# WC_Lower_v2_1.net
KiCad netlist of a schematic drawn in EAGLE
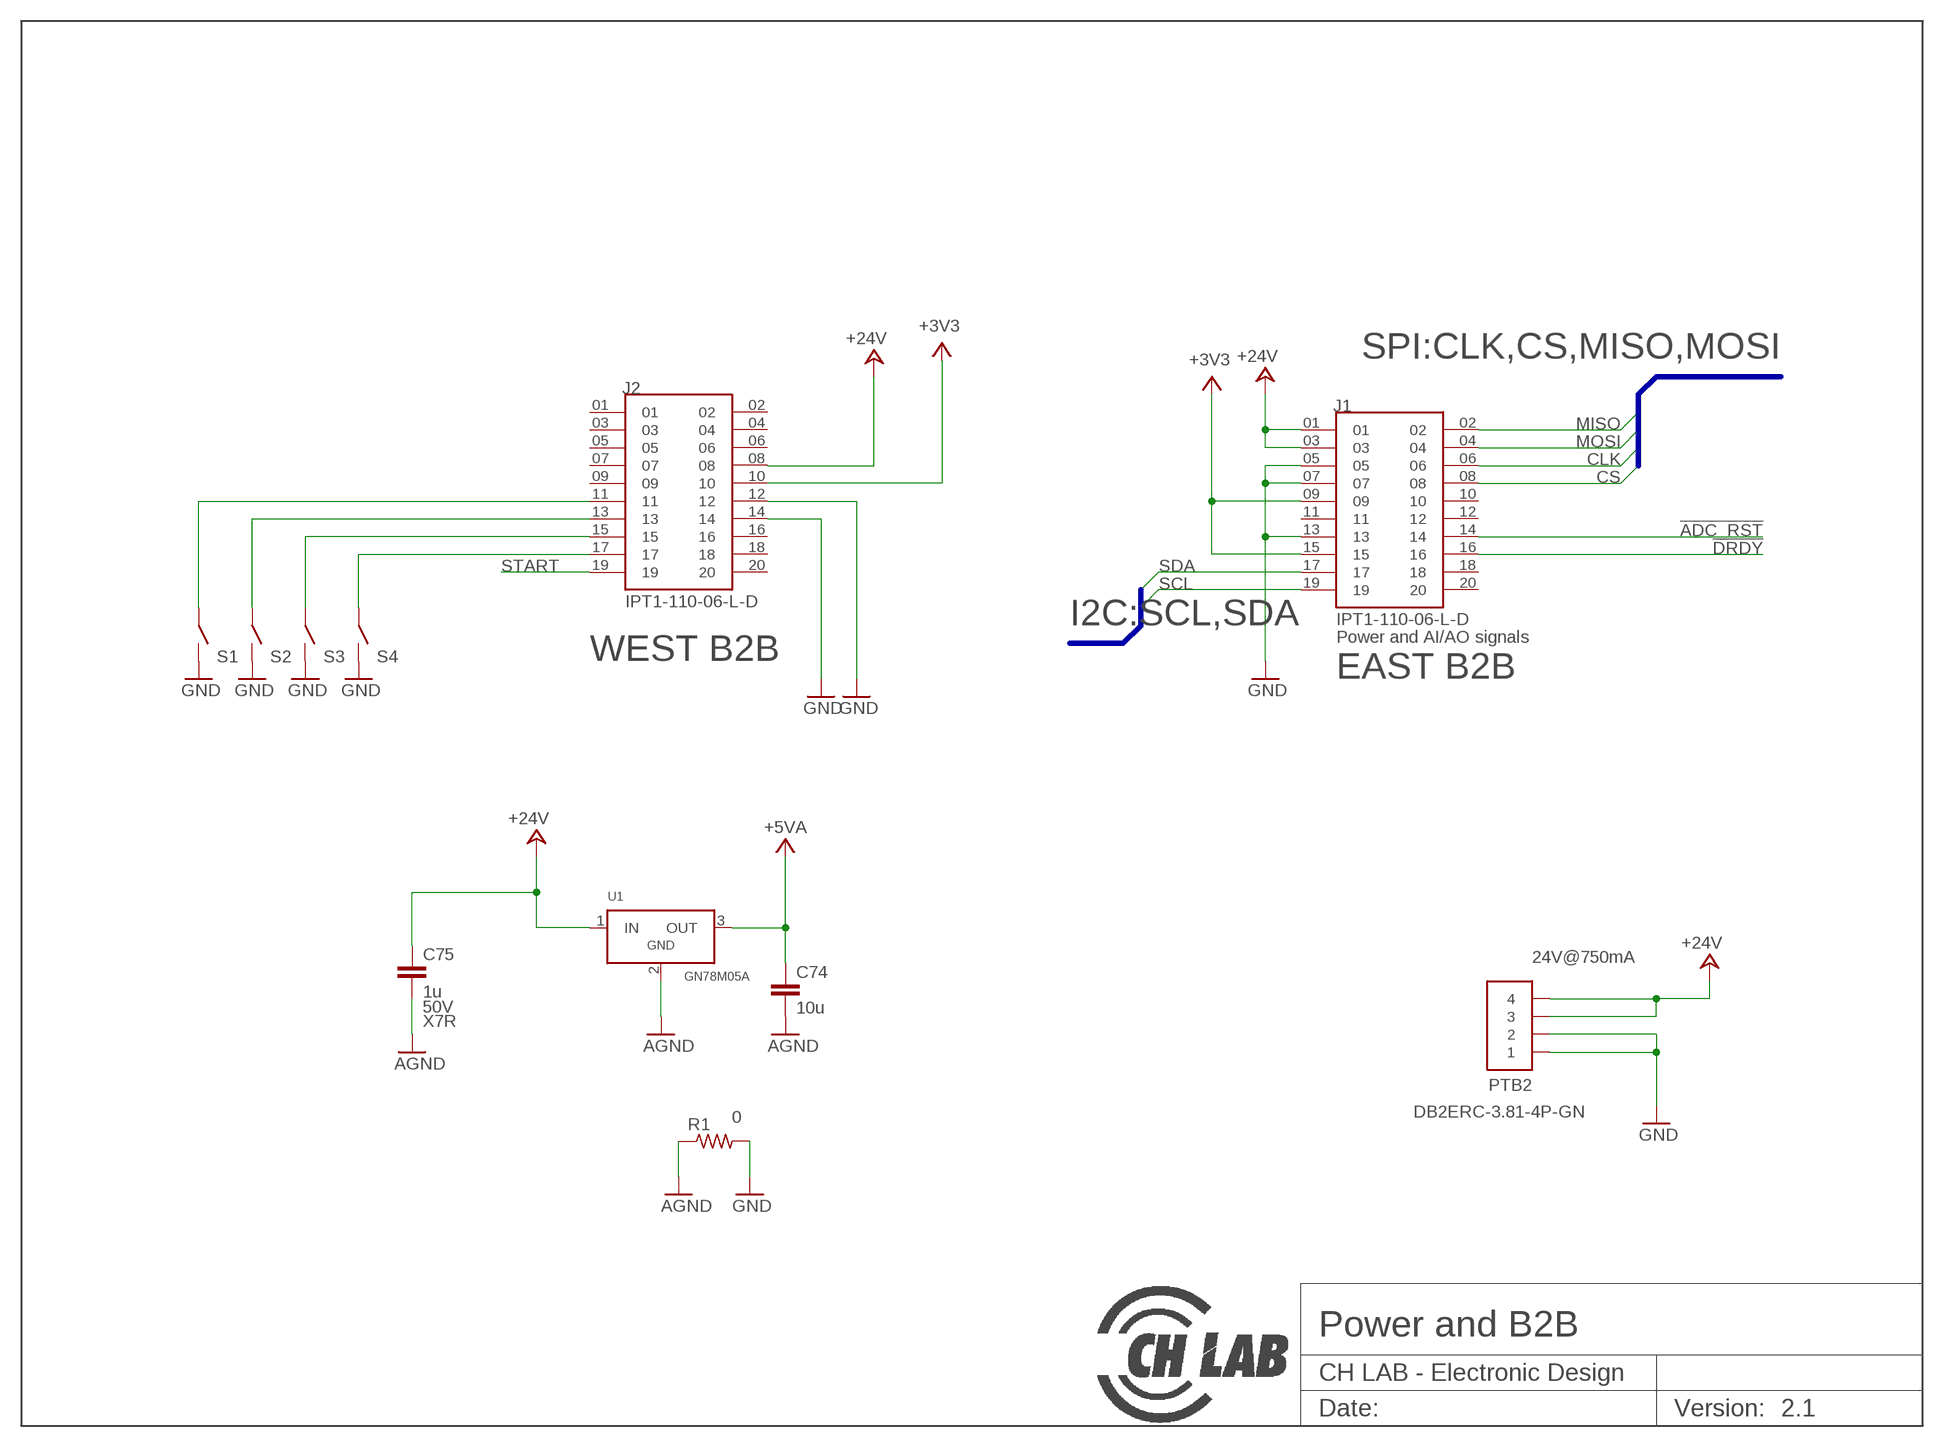
[diagram p0: schematic, sheet 1]
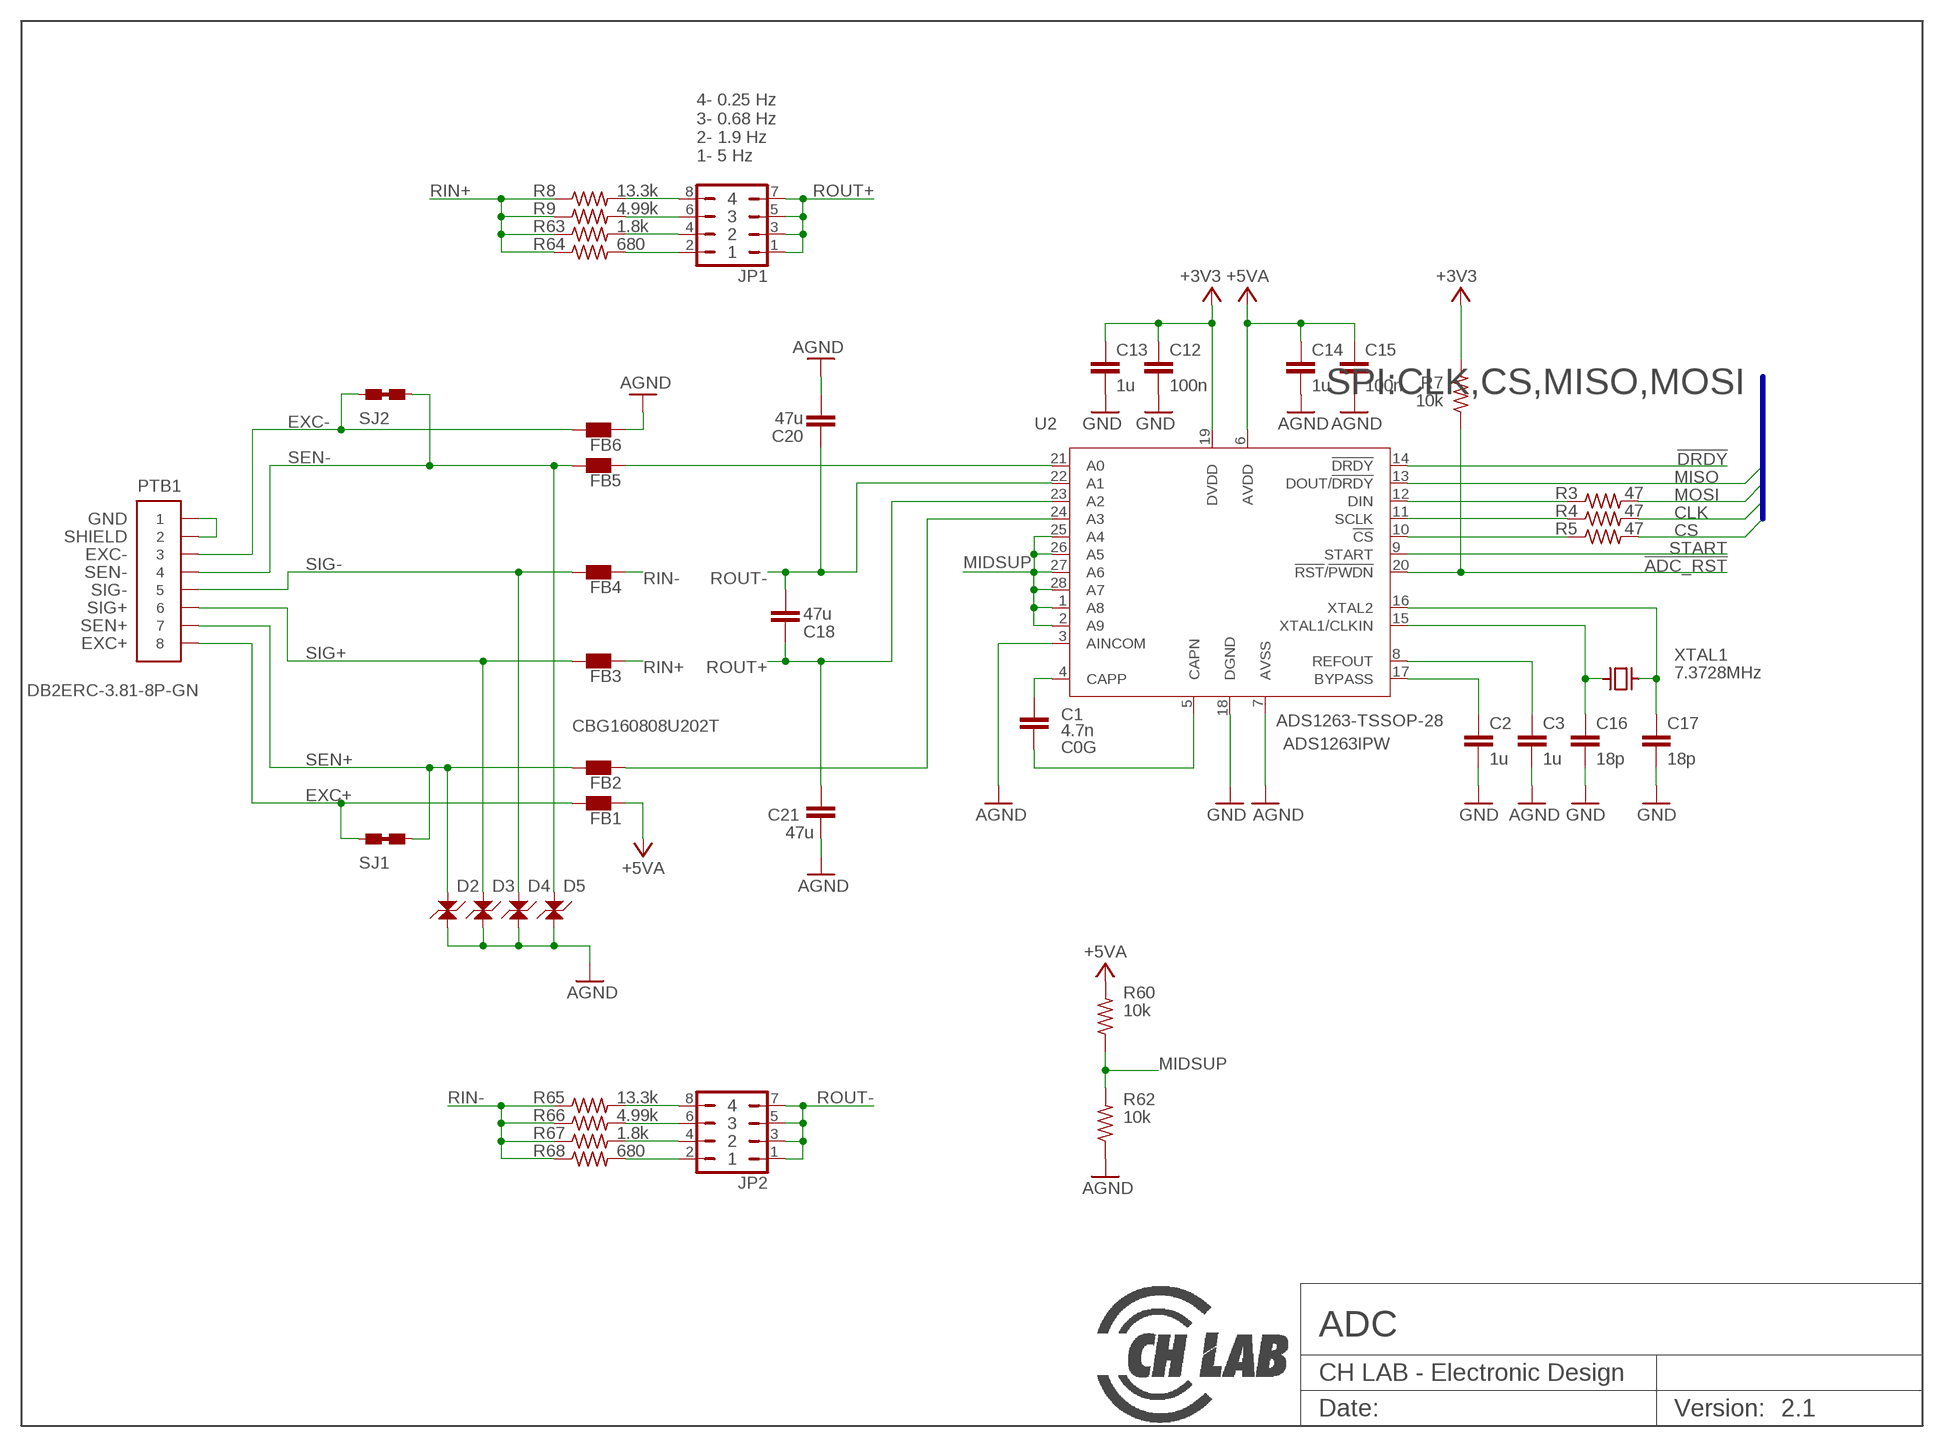
[diagram p1: schematic, sheet 2]

(export (version "E")
  (design (tool "Eeschema 10.0.6"))
  (components
    (comp (ref "C1")
      (value "4.7n")
      (footprint "eagle-import:C_0603")
      (fields (field (name "DK") "C0G"))
      (libsource (lib "eagle-import") (part "C_0603"))
    )
    (comp (ref "C2")
      (value "1u")
      (footprint "eagle-import:C_0603")
      (libsource (lib "eagle-import") (part "C_0603"))
    )
    (comp (ref "C3")
      (value "1u")
      (footprint "eagle-import:C_0603")
      (libsource (lib "eagle-import") (part "C_0603"))
    )
    (comp (ref "C12")
      (value "100n")
      (footprint "eagle-import:C_0603")
      (libsource (lib "eagle-import") (part "C_0603"))
    )
    (comp (ref "C13")
      (value "1u")
      (footprint "eagle-import:C_0603")
      (libsource (lib "eagle-import") (part "C_0603"))
    )
    (comp (ref "C14")
      (value "1u")
      (footprint "eagle-import:C_0603")
      (libsource (lib "eagle-import") (part "C_0603"))
    )
    (comp (ref "C15")
      (value "100n")
      (footprint "eagle-import:C_0603")
      (libsource (lib "eagle-import") (part "C_0603"))
    )
    (comp (ref "C16")
      (value "18p")
      (footprint "eagle-import:C_0603")
      (libsource (lib "eagle-import") (part "C_0603"))
    )
    (comp (ref "C17")
      (value "18p")
      (footprint "eagle-import:C_0603")
      (libsource (lib "eagle-import") (part "C_0603"))
    )
    (comp (ref "C18")
      (value "47u")
      (footprint "eagle-import:C_1210")
      (libsource (lib "eagle-import") (part "C_1210"))
    )
    (comp (ref "C20")
      (value "47u")
      (footprint "eagle-import:C_1210")
      (libsource (lib "eagle-import") (part "C_1210"))
    )
    (comp (ref "C21")
      (value "47u")
      (footprint "eagle-import:C_1210")
      (libsource (lib "eagle-import") (part "C_1210"))
    )
    (comp (ref "D2")
      (value "LESD5D5.0CT1G")
      (footprint "eagle-import:SOD523")
      (libsource (lib "eagle-import") (part "LESD5D5.0CT1G"))
    )
    (comp (ref "D3")
      (value "LESD5D5.0CT1G")
      (footprint "eagle-import:SOD523")
      (libsource (lib "eagle-import") (part "LESD5D5.0CT1G"))
    )
    (comp (ref "D4")
      (value "LESD5D5.0CT1G")
      (footprint "eagle-import:SOD523")
      (libsource (lib "eagle-import") (part "LESD5D5.0CT1G"))
    )
    (comp (ref "D5")
      (value "LESD5D5.0CT1G")
      (footprint "eagle-import:SOD523")
      (libsource (lib "eagle-import") (part "LESD5D5.0CT1G"))
    )
    (comp (ref "FB1")
      (value "FB_0603")
      (footprint "eagle-import:R_0603")
      (libsource (lib "eagle-import") (part "FB_0603"))
    )
    (comp (ref "FB2")
      (value "FB_0603")
      (footprint "eagle-import:R_0603")
      (libsource (lib "eagle-import") (part "FB_0603"))
    )
    (comp (ref "FB3")
      (value "FB_0603")
      (footprint "eagle-import:R_0603")
      (libsource (lib "eagle-import") (part "FB_0603"))
    )
    (comp (ref "FB4")
      (value "FB_0603")
      (footprint "eagle-import:R_0603")
      (libsource (lib "eagle-import") (part "FB_0603"))
    )
    (comp (ref "FB5")
      (value "FB_0603")
      (footprint "eagle-import:R_0603")
      (libsource (lib "eagle-import") (part "FB_0603"))
    )
    (comp (ref "FB6")
      (value "FB_0603")
      (footprint "eagle-import:R_0603")
      (libsource (lib "eagle-import") (part "FB_0603"))
    )
    (comp (ref "JP1")
      (value "CONVERT-2X4-2.54MALE")
      (footprint "eagle-import:CONN-VERT-2.54MM-2X4-MALE")
      (libsource (lib "eagle-import") (part "CONVERT-2X4-2.54MALE"))
    )
    (comp (ref "JP2")
      (value "CONVERT-2X4-2.54MALE")
      (footprint "eagle-import:CONN-VERT-2.54MM-2X4-MALE")
      (libsource (lib "eagle-import") (part "CONVERT-2X4-2.54MALE"))
    )
    (comp (ref "PTB1")
      (value "DB2ERC-3.81-8P-GN")
      (footprint "eagle-import:1803332")
      (libsource (lib "eagle-import") (part "PLUGTB-8-1803332"))
    )
    (comp (ref "R3")
      (value "47")
      (footprint "eagle-import:R_0402")
      (libsource (lib "eagle-import") (part "R_0402"))
    )
    (comp (ref "R4")
      (value "47")
      (footprint "eagle-import:R_0402")
      (libsource (lib "eagle-import") (part "R_0402"))
    )
    (comp (ref "R5")
      (value "47")
      (footprint "eagle-import:R_0402")
      (libsource (lib "eagle-import") (part "R_0402"))
    )
    (comp (ref "R7")
      (value "10k")
      (footprint "eagle-import:R_0603")
      (libsource (lib "eagle-import") (part "R_0603"))
    )
    (comp (ref "R8")
      (value "13.3k")
      (footprint "eagle-import:R_0603")
      (libsource (lib "eagle-import") (part "R_0603"))
    )
    (comp (ref "R9")
      (value "4.99k")
      (footprint "eagle-import:R_0603")
      (libsource (lib "eagle-import") (part "R_0603"))
    )
    (comp (ref "R60")
      (value "10k")
      (footprint "eagle-import:R_0603")
      (libsource (lib "eagle-import") (part "R_0603"))
    )
    (comp (ref "R62")
      (value "10k")
      (footprint "eagle-import:R_0603")
      (libsource (lib "eagle-import") (part "R_0603"))
    )
    (comp (ref "R63")
      (value "1.8k")
      (footprint "eagle-import:R_0603")
      (libsource (lib "eagle-import") (part "R_0603"))
    )
    (comp (ref "R64")
      (value "680")
      (footprint "eagle-import:R_0603")
      (libsource (lib "eagle-import") (part "R_0603"))
    )
    (comp (ref "R65")
      (value "13.3k")
      (footprint "eagle-import:R_0603")
      (libsource (lib "eagle-import") (part "R_0603"))
    )
    (comp (ref "R66")
      (value "4.99k")
      (footprint "eagle-import:R_0603")
      (libsource (lib "eagle-import") (part "R_0603"))
    )
    (comp (ref "R67")
      (value "1.8k")
      (footprint "eagle-import:R_0603")
      (libsource (lib "eagle-import") (part "R_0603"))
    )
    (comp (ref "R68")
      (value "680")
      (footprint "eagle-import:R_0603")
      (libsource (lib "eagle-import") (part "R_0603"))
    )
    (comp (ref "SJ1")
      (value "SJUMPER-NC")
      (footprint "eagle-import:SJ1")
      (libsource (lib "eagle-import") (part "SJUMPER-NC"))
    )
    (comp (ref "SJ2")
      (value "SJUMPER-NC")
      (footprint "eagle-import:SJ1")
      (libsource (lib "eagle-import") (part "SJUMPER-NC"))
    )
    (comp (ref "U2")
      (value "ADS1263-TSSOP-28")
      (footprint "eagle-import:SOP65P640X120-28N")
      (fields (field (name "MPN") "ADS1263IPW"))
      (libsource (lib "eagle-import") (part "ADS1263-TSSOP-28"))
    )
    (comp (ref "XTAL1")
      (value "7.3728MHz")
      (footprint "eagle-import:XTAL")
      (fields
        (field (name "LINK") "https://www.mouser.com/ProductDetail/ABRACON/ABLS-7.3728MHZ-K4T?qs=uDmhV2jwPReaiEAs5bxjfg%3D%3D")
        (field (name "MPN") "ABLS-7.3728MHZ-K4T")
      )
      (libsource (lib "eagle-import") (part "XTAL_11.4X4.7"))
    )
    (comp (ref "C74")
      (value "10u")
      (footprint "eagle-import:C_0805")
      (libsource (lib "eagle-import") (part "C_0805"))
    )
    (comp (ref "C75")
      (value "1u")
      (footprint "eagle-import:C_1206")
      (fields (field (name "D") "X7R") (field (name "ESR") "LOW") (field (name "V") "50V"))
      (libsource (lib "eagle-import") (part "C_1206"))
    )
    (comp (ref "J1")
      (value "IPT1-110-06-L-D")
      (footprint "eagle-import:SAMTEC_IPT1-110-06-L-D")
      (fields (field (name "MANUFACTURER") "Samtec"))
      (libsource (lib "eagle-import") (part "IPT1-110-06-L-D"))
    )
    (comp (ref "J2")
      (value "IPT1-110-06-L-D")
      (footprint "eagle-import:SAMTEC_IPT1-110-06-L-D")
      (fields (field (name "MANUFACTURER") "Samtec"))
      (libsource (lib "eagle-import") (part "IPT1-110-06-L-D"))
    )
    (comp (ref "PTB2")
      (value "DB2ERC-3.81-4P-GN")
      (footprint "eagle-import:1803293")
      (libsource (lib "eagle-import") (part "PLUGTB-4-1803293"))
    )
    (comp (ref "R1")
      (value "0")
      (footprint "eagle-import:R_0603")
      (libsource (lib "eagle-import") (part "R_0603"))
    )
    (comp (ref "S1")
      (value "TSWITCH_SMTR2")
      (footprint "eagle-import:SMTR2")
      (libsource (lib "eagle-import") (part "TSWITCH_SMTR2"))
    )
    (comp (ref "S2")
      (value "TSWITCH_SMTR2")
      (footprint "eagle-import:SMTR2")
      (libsource (lib "eagle-import") (part "TSWITCH_SMTR2"))
    )
    (comp (ref "S3")
      (value "TSWITCH_SMTR2")
      (footprint "eagle-import:SMTR2")
      (libsource (lib "eagle-import") (part "TSWITCH_SMTR2"))
    )
    (comp (ref "S4")
      (value "TSWITCH_SMTR2")
      (footprint "eagle-import:SMTR2")
      (libsource (lib "eagle-import") (part "TSWITCH_SMTR2"))
    )
    (comp (ref "U1")
      (value "GN78M05A")
      (footprint "eagle-import:TO-252")
      (libsource (lib "eagle-import") (part "GN78M05A"))
    )
  )
  (nets
    (net (code "4") (name "+3V3") (class "Default")
      (node (ref "C12") (pin "P$1") (pinfunction "1_P$1") (pintype "passive"))
      (node (ref "C13") (pin "P$1") (pinfunction "1_P$1") (pintype "passive"))
      (node (ref "J1") (pin "09") (pinfunction "09_09") (pintype "passive"))
      (node (ref "J1") (pin "15") (pinfunction "15_15") (pintype "passive"))
      (node (ref "J2") (pin "10") (pinfunction "10_10") (pintype "passive"))
      (node (ref "R7") (pin "2") (pinfunction "2_2") (pintype "passive"))
      (node (ref "U2") (pin "19") (pinfunction "DVDD_19") (pintype "power_in"))
    )
    (net (code "5") (name "+5VA") (class "Default")
      (node (ref "C14") (pin "P$1") (pinfunction "1_P$1") (pintype "passive"))
      (node (ref "C15") (pin "P$1") (pinfunction "1_P$1") (pintype "passive"))
      (node (ref "C74") (pin "P$1") (pinfunction "1_P$1") (pintype "passive"))
      (node (ref "FB1") (pin "2") (pinfunction "2_2") (pintype "passive"))
      (node (ref "R60") (pin "2") (pinfunction "2_2") (pintype "passive"))
      (node (ref "U1") (pin "3") (pinfunction "OUT_3") (pintype "power_in"))
      (node (ref "U2") (pin "6") (pinfunction "AVDD_6") (pintype "power_in"))
    )
    (net (code "6") (name "+24V") (class "Default")
      (node (ref "C75") (pin "P$1") (pinfunction "1_P$1") (pintype "passive"))
      (node (ref "J1") (pin "01") (pinfunction "01_01") (pintype "passive"))
      (node (ref "J1") (pin "03") (pinfunction "03_03") (pintype "passive"))
      (node (ref "J2") (pin "08") (pinfunction "08_08") (pintype "passive"))
      (node (ref "PTB2") (pin "P$3") (pinfunction "3_P$3") (pintype "bidirectional"))
      (node (ref "PTB2") (pin "P$4") (pinfunction "4_P$4") (pintype "bidirectional"))
      (node (ref "U1") (pin "1") (pinfunction "IN_1") (pintype "power_in"))
    )
    (net (code "10") (name "AGND") (class "Default")
      (node (ref "C14") (pin "P$2") (pinfunction "2_P$2") (pintype "passive"))
      (node (ref "C15") (pin "P$2") (pinfunction "2_P$2") (pintype "passive"))
      (node (ref "C20") (pin "P$1") (pinfunction "1_P$1") (pintype "passive"))
      (node (ref "C21") (pin "P$1") (pinfunction "1_P$1") (pintype "passive"))
      (node (ref "C3") (pin "P$2") (pinfunction "2_P$2") (pintype "passive"))
      (node (ref "C74") (pin "P$2") (pinfunction "2_P$2") (pintype "passive"))
      (node (ref "C75") (pin "P$2") (pinfunction "2_P$2") (pintype "passive"))
      (node (ref "D2") (pin "C") (pinfunction "P$2_C") (pintype "bidirectional"))
      (node (ref "D3") (pin "C") (pinfunction "P$2_C") (pintype "bidirectional"))
      (node (ref "D4") (pin "C") (pinfunction "P$2_C") (pintype "bidirectional"))
      (node (ref "D5") (pin "C") (pinfunction "P$2_C") (pintype "bidirectional"))
      (node (ref "FB6") (pin "2") (pinfunction "2_2") (pintype "passive"))
      (node (ref "R1") (pin "1") (pinfunction "1_1") (pintype "passive"))
      (node (ref "R62") (pin "1") (pinfunction "1_1") (pintype "passive"))
      (node (ref "U1") (pin "2") (pinfunction "GND_2") (pintype "power_in"))
      (node (ref "U2") (pin "3") (pinfunction "AINCOM_3") (pintype "bidirectional"))
      (node (ref "U2") (pin "7") (pinfunction "AVSS_7") (pintype "power_in"))
    )
    (net (code "11") (name "CLK") (class "Default")
      (node (ref "J1") (pin "06") (pinfunction "06_06") (pintype "passive"))
      (node (ref "R4") (pin "2") (pinfunction "2_2") (pintype "passive"))
    )
    (net (code "12") (name "CS") (class "Default")
      (node (ref "J1") (pin "08") (pinfunction "08_08") (pintype "passive"))
      (node (ref "R5") (pin "2") (pinfunction "2_2") (pintype "passive"))
    )
    (net (code "13") (name "EXC+") (class "Default")
      (node (ref "FB1") (pin "1") (pinfunction "1_1") (pintype "passive"))
      (node (ref "PTB1") (pin "P$8") (pinfunction "8_P$8") (pintype "bidirectional"))
      (node (ref "SJ1") (pin "P$1") (pinfunction "P$1_P$1") (pintype "bidirectional"))
    )
    (net (code "14") (name "EXC-") (class "Default")
      (node (ref "FB6") (pin "1") (pinfunction "1_1") (pintype "passive"))
      (node (ref "PTB1") (pin "P$3") (pinfunction "3_P$3") (pintype "bidirectional"))
      (node (ref "SJ2") (pin "P$1") (pinfunction "P$1_P$1") (pintype "bidirectional"))
    )
    (net (code "15") (name "GND") (class "Default")
      (node (ref "C12") (pin "P$2") (pinfunction "2_P$2") (pintype "passive"))
      (node (ref "C13") (pin "P$2") (pinfunction "2_P$2") (pintype "passive"))
      (node (ref "C16") (pin "P$2") (pinfunction "2_P$2") (pintype "passive"))
      (node (ref "C17") (pin "P$2") (pinfunction "2_P$2") (pintype "passive"))
      (node (ref "C2") (pin "P$2") (pinfunction "2_P$2") (pintype "passive"))
      (node (ref "J1") (pin "05") (pinfunction "05_05") (pintype "passive"))
      (node (ref "J1") (pin "07") (pinfunction "07_07") (pintype "passive"))
      (node (ref "J1") (pin "13") (pinfunction "13_13") (pintype "passive"))
      (node (ref "J2") (pin "12") (pinfunction "12_12") (pintype "passive"))
      (node (ref "J2") (pin "14") (pinfunction "14_14") (pintype "passive"))
      (node (ref "PTB2") (pin "P$1") (pinfunction "1_P$1") (pintype "bidirectional"))
      (node (ref "PTB2") (pin "P$2") (pinfunction "2_P$2") (pintype "bidirectional"))
      (node (ref "R1") (pin "2") (pinfunction "2_2") (pintype "passive"))
      (node (ref "S1") (pin "P$3") (pinfunction "P$2_P$3") (pintype "bidirectional"))
      (node (ref "S1") (pin "P$4") (pinfunction "P$2_P$4") (pintype "bidirectional"))
      (node (ref "S2") (pin "P$3") (pinfunction "P$2_P$3") (pintype "bidirectional"))
      (node (ref "S2") (pin "P$4") (pinfunction "P$2_P$4") (pintype "bidirectional"))
      (node (ref "S3") (pin "P$3") (pinfunction "P$2_P$3") (pintype "bidirectional"))
      (node (ref "S3") (pin "P$4") (pinfunction "P$2_P$4") (pintype "bidirectional"))
      (node (ref "S4") (pin "P$3") (pinfunction "P$2_P$3") (pintype "bidirectional"))
      (node (ref "S4") (pin "P$4") (pinfunction "P$2_P$4") (pintype "bidirectional"))
      (node (ref "U2") (pin "18") (pinfunction "DGND_18") (pintype "power_in"))
    )
    (net (code "16") (name "MIDSUP") (class "Default")
      (node (ref "R60") (pin "1") (pinfunction "1_1") (pintype "passive"))
      (node (ref "R62") (pin "2") (pinfunction "2_2") (pintype "passive"))
      (node (ref "U2") (pin "1") (pinfunction "A8_1") (pintype "bidirectional"))
      (node (ref "U2") (pin "2") (pinfunction "A9_2") (pintype "bidirectional"))
      (node (ref "U2") (pin "25") (pinfunction "A4_25") (pintype "bidirectional"))
      (node (ref "U2") (pin "26") (pinfunction "A5_26") (pintype "bidirectional"))
      (node (ref "U2") (pin "27") (pinfunction "A6_27") (pintype "bidirectional"))
      (node (ref "U2") (pin "28") (pinfunction "A7_28") (pintype "bidirectional"))
    )
    (net (code "17") (name "MISO") (class "Default")
      (node (ref "J1") (pin "02") (pinfunction "02_02") (pintype "passive"))
      (node (ref "U2") (pin "13") (pinfunction "DOUT/~{DRDY}_13") (pintype "output"))
    )
    (net (code "18") (name "MOSI") (class "Default")
      (node (ref "J1") (pin "04") (pinfunction "04_04") (pintype "passive"))
      (node (ref "R3") (pin "2") (pinfunction "2_2") (pintype "passive"))
    )
    (net (code "19") (name "Net-(C1-1)") (class "Default")
      (node (ref "C1") (pin "P$1") (pinfunction "1_P$1") (pintype "passive"))
      (node (ref "U2") (pin "4") (pinfunction "CAPP_4") (pintype "output"))
    )
    (net (code "20") (name "Net-(C1-2)") (class "Default")
      (node (ref "C1") (pin "P$2") (pinfunction "2_P$2") (pintype "passive"))
      (node (ref "U2") (pin "5") (pinfunction "CAPN_5") (pintype "output"))
    )
    (net (code "21") (name "Net-(C2-1)") (class "Default")
      (node (ref "C2") (pin "P$1") (pinfunction "1_P$1") (pintype "passive"))
      (node (ref "U2") (pin "17") (pinfunction "BYPASS_17") (pintype "output"))
    )
    (net (code "22") (name "Net-(C3-1)") (class "Default")
      (node (ref "C3") (pin "P$1") (pinfunction "1_P$1") (pintype "passive"))
      (node (ref "U2") (pin "8") (pinfunction "REFOUT_8") (pintype "output"))
    )
    (net (code "23") (name "Net-(C16-1)") (class "Default")
      (node (ref "C16") (pin "P$1") (pinfunction "1_P$1") (pintype "passive"))
      (node (ref "U2") (pin "15") (pinfunction "XTAL1/CLKIN_15") (pintype "input"))
      (node (ref "XTAL1") (pin "1") (pinfunction "X1_1") (pintype "passive"))
    )
    (net (code "24") (name "Net-(C17-1)") (class "Default")
      (node (ref "C17") (pin "P$1") (pinfunction "1_P$1") (pintype "passive"))
      (node (ref "U2") (pin "16") (pinfunction "XTAL2_16") (pintype "input"))
      (node (ref "XTAL1") (pin "2") (pinfunction "X2_2") (pintype "passive"))
    )
    (net (code "25") (name "Net-(J2-Pad11)") (class "Default")
      (node (ref "J2") (pin "11") (pinfunction "11_11") (pintype "passive"))
      (node (ref "S1") (pin "P$1") (pinfunction "P$1_P$1") (pintype "bidirectional"))
      (node (ref "S1") (pin "P$2") (pinfunction "P$1_P$2") (pintype "bidirectional"))
    )
    (net (code "26") (name "Net-(J2-Pad13)") (class "Default")
      (node (ref "J2") (pin "13") (pinfunction "13_13") (pintype "passive"))
      (node (ref "S2") (pin "P$1") (pinfunction "P$1_P$1") (pintype "bidirectional"))
      (node (ref "S2") (pin "P$2") (pinfunction "P$1_P$2") (pintype "bidirectional"))
    )
    (net (code "27") (name "Net-(J2-Pad15)") (class "Default")
      (node (ref "J2") (pin "15") (pinfunction "15_15") (pintype "passive"))
      (node (ref "S3") (pin "P$1") (pinfunction "P$1_P$1") (pintype "bidirectional"))
      (node (ref "S3") (pin "P$2") (pinfunction "P$1_P$2") (pintype "bidirectional"))
    )
    (net (code "28") (name "Net-(J2-Pad17)") (class "Default")
      (node (ref "J2") (pin "17") (pinfunction "17_17") (pintype "passive"))
      (node (ref "S4") (pin "P$1") (pinfunction "P$1_P$1") (pintype "bidirectional"))
      (node (ref "S4") (pin "P$2") (pinfunction "P$1_P$2") (pintype "bidirectional"))
    )
    (net (code "29") (name "Net-(JP1-Pad2)") (class "Default")
      (node (ref "JP1") (pin "2") (pinfunction "2_2") (pintype "passive"))
      (node (ref "R64") (pin "2") (pinfunction "2_2") (pintype "passive"))
    )
    (net (code "30") (name "Net-(JP1-Pad4)") (class "Default")
      (node (ref "JP1") (pin "4") (pinfunction "4_4") (pintype "passive"))
      (node (ref "R63") (pin "2") (pinfunction "2_2") (pintype "passive"))
    )
    (net (code "31") (name "Net-(JP1-Pad6)") (class "Default")
      (node (ref "JP1") (pin "6") (pinfunction "6_6") (pintype "passive"))
      (node (ref "R9") (pin "2") (pinfunction "2_2") (pintype "passive"))
    )
    (net (code "32") (name "Net-(JP1-Pad8)") (class "Default")
      (node (ref "JP1") (pin "8") (pinfunction "8_8") (pintype "passive"))
      (node (ref "R8") (pin "2") (pinfunction "2_2") (pintype "passive"))
    )
    (net (code "33") (name "Net-(JP2-Pad2)") (class "Default")
      (node (ref "JP2") (pin "2") (pinfunction "2_2") (pintype "passive"))
      (node (ref "R68") (pin "2") (pinfunction "2_2") (pintype "passive"))
    )
    (net (code "34") (name "Net-(JP2-Pad4)") (class "Default")
      (node (ref "JP2") (pin "4") (pinfunction "4_4") (pintype "passive"))
      (node (ref "R67") (pin "2") (pinfunction "2_2") (pintype "passive"))
    )
    (net (code "35") (name "Net-(JP2-Pad6)") (class "Default")
      (node (ref "JP2") (pin "6") (pinfunction "6_6") (pintype "passive"))
      (node (ref "R66") (pin "2") (pinfunction "2_2") (pintype "passive"))
    )
    (net (code "36") (name "Net-(JP2-Pad8)") (class "Default")
      (node (ref "JP2") (pin "8") (pinfunction "8_8") (pintype "passive"))
      (node (ref "R65") (pin "2") (pinfunction "2_2") (pintype "passive"))
    )
    (net (code "37") (name "Net-(PTB1-1)") (class "Default")
      (node (ref "PTB1") (pin "P$1") (pinfunction "1_P$1") (pintype "bidirectional"))
      (node (ref "PTB1") (pin "P$2") (pinfunction "2_P$2") (pintype "bidirectional"))
    )
    (net (code "38") (name "Net-(U2-A0)") (class "Default")
      (node (ref "FB5") (pin "2") (pinfunction "2_2") (pintype "passive"))
      (node (ref "U2") (pin "21") (pinfunction "A0_21") (pintype "bidirectional"))
    )
    (net (code "39") (name "Net-(U2-A3)") (class "Default")
      (node (ref "FB2") (pin "2") (pinfunction "2_2") (pintype "passive"))
      (node (ref "U2") (pin "24") (pinfunction "A3_24") (pintype "bidirectional"))
    )
    (net (code "40") (name "Net-(U2-DIN)") (class "Default")
      (node (ref "R3") (pin "1") (pinfunction "1_1") (pintype "passive"))
      (node (ref "U2") (pin "12") (pinfunction "DIN_12") (pintype "input"))
    )
    (net (code "41") (name "Net-(U2-SCLK)") (class "Default")
      (node (ref "R4") (pin "1") (pinfunction "1_1") (pintype "passive"))
      (node (ref "U2") (pin "11") (pinfunction "SCLK_11") (pintype "input"))
    )
    (net (code "42") (name "Net-(U2-~{CS})") (class "Default")
      (node (ref "R5") (pin "1") (pinfunction "1_1") (pintype "passive"))
      (node (ref "U2") (pin "10") (pinfunction "~{CS}_10") (pintype "input"))
    )
    (net (code "43") (name "RIN+") (class "Default")
      (node (ref "FB3") (pin "2") (pinfunction "2_2") (pintype "passive"))
      (node (ref "R63") (pin "1") (pinfunction "1_1") (pintype "passive"))
      (node (ref "R64") (pin "1") (pinfunction "1_1") (pintype "passive"))
      (node (ref "R8") (pin "1") (pinfunction "1_1") (pintype "passive"))
      (node (ref "R9") (pin "1") (pinfunction "1_1") (pintype "passive"))
    )
    (net (code "44") (name "RIN-") (class "Default")
      (node (ref "FB4") (pin "2") (pinfunction "2_2") (pintype "passive"))
      (node (ref "R65") (pin "1") (pinfunction "1_1") (pintype "passive"))
      (node (ref "R66") (pin "1") (pinfunction "1_1") (pintype "passive"))
      (node (ref "R67") (pin "1") (pinfunction "1_1") (pintype "passive"))
      (node (ref "R68") (pin "1") (pinfunction "1_1") (pintype "passive"))
    )
    (net (code "45") (name "ROUT+") (class "Default")
      (node (ref "C18") (pin "P$1") (pinfunction "1_P$1") (pintype "passive"))
      (node (ref "C21") (pin "P$2") (pinfunction "2_P$2") (pintype "passive"))
      (node (ref "JP1") (pin "1") (pinfunction "1_1") (pintype "passive"))
      (node (ref "JP1") (pin "3") (pinfunction "3_3") (pintype "passive"))
      (node (ref "JP1") (pin "5") (pinfunction "5_5") (pintype "passive"))
      (node (ref "JP1") (pin "7") (pinfunction "7_7") (pintype "passive"))
      (node (ref "U2") (pin "23") (pinfunction "A2_23") (pintype "bidirectional"))
    )
    (net (code "46") (name "ROUT-") (class "Default")
      (node (ref "C18") (pin "P$2") (pinfunction "2_P$2") (pintype "passive"))
      (node (ref "C20") (pin "P$2") (pinfunction "2_P$2") (pintype "passive"))
      (node (ref "JP2") (pin "1") (pinfunction "1_1") (pintype "passive"))
      (node (ref "JP2") (pin "3") (pinfunction "3_3") (pintype "passive"))
      (node (ref "JP2") (pin "5") (pinfunction "5_5") (pintype "passive"))
      (node (ref "JP2") (pin "7") (pinfunction "7_7") (pintype "passive"))
      (node (ref "U2") (pin "22") (pinfunction "A1_22") (pintype "bidirectional"))
    )
    (net (code "47") (name "SCL") (class "Default")
      (node (ref "J1") (pin "19") (pinfunction "19_19") (pintype "passive"))
    )
    (net (code "48") (name "SDA") (class "Default")
      (node (ref "J1") (pin "17") (pinfunction "17_17") (pintype "passive"))
    )
    (net (code "49") (name "SEN+") (class "Default")
      (node (ref "D2") (pin "A") (pinfunction "P$1_A") (pintype "bidirectional"))
      (node (ref "FB2") (pin "1") (pinfunction "1_1") (pintype "passive"))
      (node (ref "PTB1") (pin "P$7") (pinfunction "7_P$7") (pintype "bidirectional"))
      (node (ref "SJ1") (pin "P$2") (pinfunction "P$2_P$2") (pintype "bidirectional"))
    )
    (net (code "50") (name "SEN-") (class "Default")
      (node (ref "D5") (pin "A") (pinfunction "P$1_A") (pintype "bidirectional"))
      (node (ref "FB5") (pin "1") (pinfunction "1_1") (pintype "passive"))
      (node (ref "PTB1") (pin "P$4") (pinfunction "4_P$4") (pintype "bidirectional"))
      (node (ref "SJ2") (pin "P$2") (pinfunction "P$2_P$2") (pintype "bidirectional"))
    )
    (net (code "51") (name "SIG+") (class "Default")
      (node (ref "D3") (pin "A") (pinfunction "P$1_A") (pintype "bidirectional"))
      (node (ref "FB3") (pin "1") (pinfunction "1_1") (pintype "passive"))
      (node (ref "PTB1") (pin "P$6") (pinfunction "6_P$6") (pintype "bidirectional"))
    )
    (net (code "52") (name "SIG-") (class "Default")
      (node (ref "D4") (pin "A") (pinfunction "P$1_A") (pintype "bidirectional"))
      (node (ref "FB4") (pin "1") (pinfunction "1_1") (pintype "passive"))
      (node (ref "PTB1") (pin "P$5") (pinfunction "5_P$5") (pintype "bidirectional"))
    )
    (net (code "53") (name "START") (class "Default")
      (node (ref "J2") (pin "19") (pinfunction "19_19") (pintype "passive"))
      (node (ref "U2") (pin "9") (pinfunction "START_9") (pintype "input"))
    )
    (net (code "54") (name "unconnected-(J1-Pad10)") (class "Default")
      (node (ref "J1") (pin "10") (pinfunction "10_10") (pintype "passive"))
    )
    (net (code "55") (name "unconnected-(J1-Pad11)") (class "Default")
      (node (ref "J1") (pin "11") (pinfunction "11_11") (pintype "passive"))
    )
    (net (code "56") (name "unconnected-(J1-Pad12)") (class "Default")
      (node (ref "J1") (pin "12") (pinfunction "12_12") (pintype "passive"))
    )
    (net (code "57") (name "unconnected-(J1-Pad18)") (class "Default")
      (node (ref "J1") (pin "18") (pinfunction "18_18") (pintype "passive"))
    )
    (net (code "58") (name "unconnected-(J1-Pad20)") (class "Default")
      (node (ref "J1") (pin "20") (pinfunction "20_20") (pintype "passive"))
    )
    (net (code "59") (name "unconnected-(J2-Pad01)") (class "Default")
      (node (ref "J2") (pin "01") (pinfunction "01_01") (pintype "passive"))
    )
    (net (code "60") (name "unconnected-(J2-Pad02)") (class "Default")
      (node (ref "J2") (pin "02") (pinfunction "02_02") (pintype "passive"))
    )
    (net (code "61") (name "unconnected-(J2-Pad03)") (class "Default")
      (node (ref "J2") (pin "03") (pinfunction "03_03") (pintype "passive"))
    )
    (net (code "62") (name "unconnected-(J2-Pad04)") (class "Default")
      (node (ref "J2") (pin "04") (pinfunction "04_04") (pintype "passive"))
    )
    (net (code "63") (name "unconnected-(J2-Pad05)") (class "Default")
      (node (ref "J2") (pin "05") (pinfunction "05_05") (pintype "passive"))
    )
    (net (code "64") (name "unconnected-(J2-Pad06)") (class "Default")
      (node (ref "J2") (pin "06") (pinfunction "06_06") (pintype "passive"))
    )
    (net (code "65") (name "unconnected-(J2-Pad07)") (class "Default")
      (node (ref "J2") (pin "07") (pinfunction "07_07") (pintype "passive"))
    )
    (net (code "66") (name "unconnected-(J2-Pad09)") (class "Default")
      (node (ref "J2") (pin "09") (pinfunction "09_09") (pintype "passive"))
    )
    (net (code "67") (name "unconnected-(J2-Pad16)") (class "Default")
      (node (ref "J2") (pin "16") (pinfunction "16_16") (pintype "passive"))
    )
    (net (code "68") (name "unconnected-(J2-Pad18)") (class "Default")
      (node (ref "J2") (pin "18") (pinfunction "18_18") (pintype "passive"))
    )
    (net (code "69") (name "unconnected-(J2-Pad20)") (class "Default")
      (node (ref "J2") (pin "20") (pinfunction "20_20") (pintype "passive"))
    )
    (net (code "70") (name "~{ADC_RST}") (class "Default")
      (node (ref "J1") (pin "14") (pinfunction "14_14") (pintype "passive"))
      (node (ref "R7") (pin "1") (pinfunction "1_1") (pintype "passive"))
      (node (ref "U2") (pin "20") (pinfunction "~{RST}/~{PWDN}_20") (pintype "input"))
    )
    (net (code "71") (name "~{DRDY}") (class "Default")
      (node (ref "J1") (pin "16") (pinfunction "16_16") (pintype "passive"))
      (node (ref "U2") (pin "14") (pinfunction "~{DRDY}_14") (pintype "output"))
    )
  )
)
